# Down_Main_Board.net
KiCad netlist of a schematic drawn in EAGLE
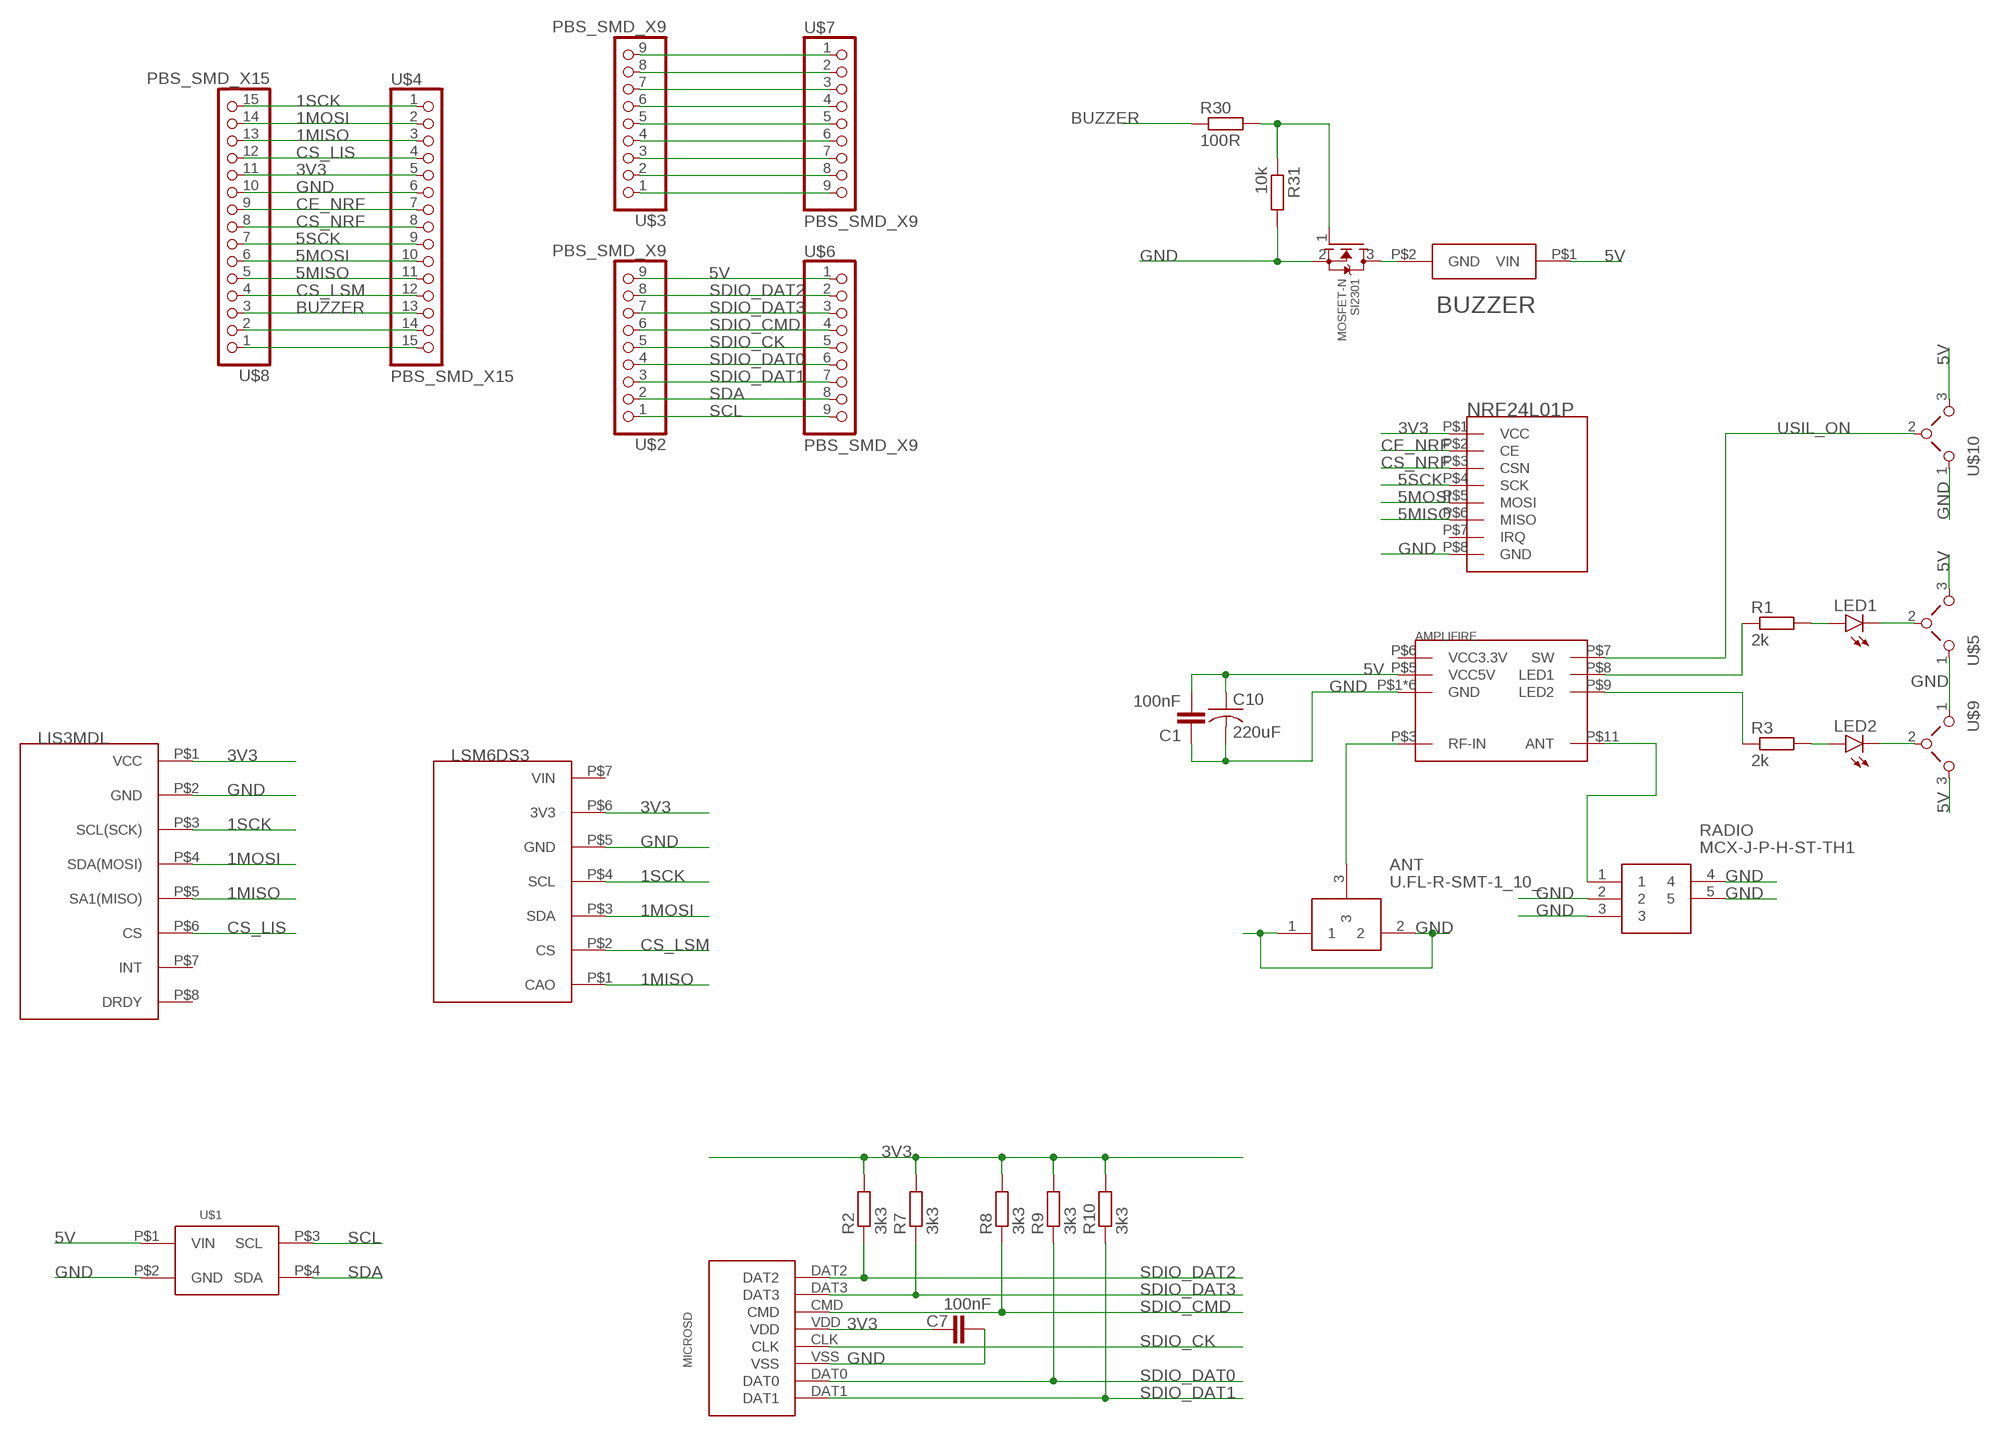
[diagram p0: schematic, sheet 1]

(export (version "E")
  (design (tool "Eeschema 10.0.6"))
  (components
    (comp (ref "AMPLIFIRE")
      (value "XQ-02A")
      (footprint "eagle-import:XQ-02A")
      (libsource (lib "eagle-import") (part "XQ-02A"))
    )
    (comp (ref "ANT")
      (value "U.FL-R-SMT-1_10_")
      (footprint "eagle-import:U.FL-R-SMT-1(10)")
      (fields
        (field (name "ARROW_PART_NUMBER") "U.FL-R-SMT-1(10)")
        (field (name "MOUSER_PART_NUMBER") "798-U.FL-R-SMT-110")
      )
      (libsource (lib "eagle-import") (part "U.FL-R-SMT-1_10_"))
    )
    (comp (ref "BUZZER")
      (value "BUZZERS8R6")
      (footprint "eagle-import:BUZZER-S8R12")
      (libsource (lib "eagle-import") (part "BUZZERS8R6"))
    )
    (comp (ref "C1")
      (value "100nF")
      (footprint "eagle-import:C0603")
      (libsource (lib "eagle-import") (part "C-EUC0603"))
    )
    (comp (ref "C7")
      (value "100nF")
      (footprint "eagle-import:C0603")
      (libsource (lib "eagle-import") (part "C-EUC0603"))
    )
    (comp (ref "C10")
      (value "220uF")
      (footprint "eagle-import:ECAP220-CMD")
      (libsource (lib "eagle-import") (part "ECAPECAP220"))
    )
    (comp (ref "LED1")
      (value "LEDCHIPLED_0603")
      (footprint "eagle-import:CHIPLED_0603")
      (libsource (lib "eagle-import") (part "LEDCHIPLED_0603"))
    )
    (comp (ref "LED2")
      (value "LEDCHIPLED_0603")
      (footprint "eagle-import:CHIPLED_0603")
      (libsource (lib "eagle-import") (part "LEDCHIPLED_0603"))
    )
    (comp (ref "LIS3MDL")
      (value "LIS3MDL-CJMCUбез_отв.")
      (footprint "eagle-import:LIS3MDL-CGMSU-NB2023-1")
      (libsource (lib "eagle-import") (part "LIS3MDL-CJMCUбез_отв."))
    )
    (comp (ref "LSM6DS3")
      (value "LSM6DS3-GY-NB2023")
      (footprint "eagle-import:LSM6DS3-GY-NB2023")
      (libsource (lib "eagle-import") (part "LSM6DS3-GY-NB2023"))
    )
    (comp (ref "MICROSD")
      (value "SD")
      (footprint "eagle-import:SD")
      (libsource (lib "eagle-import") (part "SD"))
    )
    (comp (ref "NRF24L01P")
      (value "NRF24L01_ML01SP4")
      (footprint "eagle-import:NRF24L01_ML01SP4")
      (libsource (lib "eagle-import") (part "NRF24L01_ML01SP4"))
    )
    (comp (ref "R1")
      (value "2k")
      (footprint "eagle-import:R0603")
      (libsource (lib "eagle-import") (part "R-EU_R0603"))
    )
    (comp (ref "R2")
      (value "3k3")
      (footprint "eagle-import:R0603")
      (libsource (lib "eagle-import") (part "R-EU_R0603"))
    )
    (comp (ref "R3")
      (value "2k")
      (footprint "eagle-import:R0603")
      (libsource (lib "eagle-import") (part "R-EU_R0603"))
    )
    (comp (ref "R7")
      (value "3k3")
      (footprint "eagle-import:R0603")
      (libsource (lib "eagle-import") (part "R-EU_R0603"))
    )
    (comp (ref "R8")
      (value "3k3")
      (footprint "eagle-import:R0603")
      (libsource (lib "eagle-import") (part "R-EU_R0603"))
    )
    (comp (ref "R9")
      (value "3k3")
      (footprint "eagle-import:R0603")
      (libsource (lib "eagle-import") (part "R-EU_R0603"))
    )
    (comp (ref "R10")
      (value "3k3")
      (footprint "eagle-import:R0603")
      (libsource (lib "eagle-import") (part "R-EU_R0603"))
    )
    (comp (ref "R30")
      (value "100R")
      (footprint "eagle-import:R0603")
      (libsource (lib "eagle-import") (part "R-EU_R0603"))
    )
    (comp (ref "R31")
      (value "10k")
      (footprint "eagle-import:R0603")
      (libsource (lib "eagle-import") (part "R-EU_R0603"))
    )
    (comp (ref "RADIO")
      (value "MCX-J-P-H-ST-TH1")
      (footprint "eagle-import:MCXJPHSTTH1")
      (fields (field (name "MOUSER_PART_NUMBER") "200-MCXJPHSTTH1"))
      (libsource (lib "eagle-import") (part "MCX-J-P-H-ST-TH1"))
    )
    (comp (ref "SI2301")
      (value "MOSFET-N")
      (footprint "eagle-import:SOT23-3")
      (libsource (lib "eagle-import") (part "MOSFET-N"))
    )
    (comp (ref "U$1")
      (value "BME280BME280-PINS-ONLY")
      (footprint "eagle-import:BME280-PINS-ONLY")
      (libsource (lib "eagle-import") (part "BME280BME280-PINS-ONLY"))
    )
    (comp (ref "U$2")
      (value "PBS_SMD_X9")
      (footprint "eagle-import:PBS_SMD_X9")
      (libsource (lib "eagle-import") (part "PBS_SMD_X9"))
    )
    (comp (ref "U$3")
      (value "PBS_SMD_X9")
      (footprint "eagle-import:PBS_SMD_X9")
      (libsource (lib "eagle-import") (part "PBS_SMD_X9"))
    )
    (comp (ref "U$4")
      (value "PBS_SMD_X15")
      (footprint "eagle-import:PBD_SMD_X15")
      (libsource (lib "eagle-import") (part "PBS_SMD_X15"))
    )
    (comp (ref "U$5")
      (value "VIAS-SELECT")
      (footprint "eagle-import:VIAS-SELECT")
      (libsource (lib "eagle-import") (part "VIAS-SELECT"))
    )
    (comp (ref "U$6")
      (value "PBS_SMD_X9")
      (footprint "eagle-import:PBS_SMD_X9")
      (libsource (lib "eagle-import") (part "PBS_SMD_X9"))
    )
    (comp (ref "U$7")
      (value "PBS_SMD_X9")
      (footprint "eagle-import:PBS_SMD_X9")
      (libsource (lib "eagle-import") (part "PBS_SMD_X9"))
    )
    (comp (ref "U$8")
      (value "PBS_SMD_X15")
      (footprint "eagle-import:PBD_SMD_X15")
      (libsource (lib "eagle-import") (part "PBS_SMD_X15"))
    )
    (comp (ref "U$9")
      (value "VIAS-SELECT")
      (footprint "eagle-import:VIAS-SELECT")
      (libsource (lib "eagle-import") (part "VIAS-SELECT"))
    )
    (comp (ref "U$10")
      (value "VIAS-SELECT")
      (footprint "eagle-import:VIAS-SELECT")
      (libsource (lib "eagle-import") (part "VIAS-SELECT"))
    )
  )
  (nets
    (net (code "1") (name "/1MISO") (class "Default")
      (node (ref "LIS3MDL") (pin "P$5") (pinfunction "SA1(MISO)_P$5") (pintype "bidirectional"))
      (node (ref "LSM6DS3") (pin "P$1") (pinfunction "CAO_P$1") (pintype "bidirectional"))
      (node (ref "U$4") (pin "3") (pinfunction "3_3") (pintype "passive"))
      (node (ref "U$8") (pin "13") (pinfunction "13_13") (pintype "passive"))
    )
    (net (code "2") (name "/1MOSI") (class "Default")
      (node (ref "LIS3MDL") (pin "P$4") (pinfunction "SDA(MOSI)_P$4") (pintype "bidirectional"))
      (node (ref "LSM6DS3") (pin "P$3") (pinfunction "SDA_P$3") (pintype "bidirectional"))
      (node (ref "U$4") (pin "2") (pinfunction "2_2") (pintype "passive"))
      (node (ref "U$8") (pin "14") (pinfunction "14_14") (pintype "passive"))
    )
    (net (code "3") (name "/1SCK") (class "Default")
      (node (ref "LIS3MDL") (pin "P$3") (pinfunction "SCL(SCK)_P$3") (pintype "bidirectional"))
      (node (ref "LSM6DS3") (pin "P$4") (pinfunction "SCL_P$4") (pintype "bidirectional"))
      (node (ref "U$4") (pin "1") (pinfunction "1_1") (pintype "passive"))
      (node (ref "U$8") (pin "15") (pinfunction "15_15") (pintype "passive"))
    )
    (net (code "4") (name "/3V3") (class "Default")
      (node (ref "C7") (pin "2") (pinfunction "2_2") (pintype "passive"))
      (node (ref "LIS3MDL") (pin "P$1") (pinfunction "VCC_P$1") (pintype "bidirectional"))
      (node (ref "LSM6DS3") (pin "P$6") (pinfunction "3V3_P$6") (pintype "bidirectional"))
      (node (ref "MICROSD") (pin "VDD") (pinfunction "VDD_VDD") (pintype "bidirectional"))
      (node (ref "NRF24L01P") (pin "P$1") (pinfunction "VCC_P$1") (pintype "bidirectional"))
      (node (ref "R10") (pin "2") (pinfunction "2_2") (pintype "passive"))
      (node (ref "R2") (pin "2") (pinfunction "2_2") (pintype "passive"))
      (node (ref "R7") (pin "2") (pinfunction "2_2") (pintype "passive"))
      (node (ref "R8") (pin "2") (pinfunction "2_2") (pintype "passive"))
      (node (ref "R9") (pin "2") (pinfunction "2_2") (pintype "passive"))
      (node (ref "U$4") (pin "5") (pinfunction "5_5") (pintype "passive"))
      (node (ref "U$8") (pin "11") (pinfunction "11_11") (pintype "passive"))
    )
    (net (code "5") (name "/5MISO") (class "Default")
      (node (ref "NRF24L01P") (pin "P$6") (pinfunction "MISO_P$6") (pintype "bidirectional"))
      (node (ref "U$4") (pin "11") (pinfunction "11_11") (pintype "passive"))
      (node (ref "U$8") (pin "5") (pinfunction "5_5") (pintype "passive"))
    )
    (net (code "6") (name "/5MOSI") (class "Default")
      (node (ref "NRF24L01P") (pin "P$5") (pinfunction "MOSI_P$5") (pintype "bidirectional"))
      (node (ref "U$4") (pin "10") (pinfunction "10_10") (pintype "passive"))
      (node (ref "U$8") (pin "6") (pinfunction "6_6") (pintype "passive"))
    )
    (net (code "7") (name "/5SCK") (class "Default")
      (node (ref "NRF24L01P") (pin "P$4") (pinfunction "SCK_P$4") (pintype "bidirectional"))
      (node (ref "U$4") (pin "9") (pinfunction "9_9") (pintype "passive"))
      (node (ref "U$8") (pin "7") (pinfunction "7_7") (pintype "passive"))
    )
    (net (code "8") (name "/5V") (class "Default")
      (node (ref "AMPLIFIRE") (pin "P$5") (pinfunction "VCC5V_P$5") (pintype "bidirectional"))
      (node (ref "BUZZER") (pin "P$1") (pinfunction "VIN_P$1") (pintype "bidirectional"))
      (node (ref "C1") (pin "2") (pinfunction "2_2") (pintype "passive"))
      (node (ref "C10") (pin "P$1") (pinfunction "1_P$1") (pintype "passive"))
      (node (ref "U$1") (pin "P$1") (pinfunction "VIN_P$1") (pintype "bidirectional"))
      (node (ref "U$10") (pin "3") (pinfunction "RIGHT_3") (pintype "passive"))
      (node (ref "U$2") (pin "9") (pinfunction "9_9") (pintype "passive"))
      (node (ref "U$5") (pin "3") (pinfunction "RIGHT_3") (pintype "passive"))
      (node (ref "U$6") (pin "1") (pinfunction "1_1") (pintype "passive"))
      (node (ref "U$9") (pin "3") (pinfunction "RIGHT_3") (pintype "passive"))
    )
    (net (code "9") (name "/BUZZER") (class "Default")
      (node (ref "R30") (pin "1") (pinfunction "1_1") (pintype "passive"))
      (node (ref "U$4") (pin "13") (pinfunction "13_13") (pintype "passive"))
      (node (ref "U$8") (pin "3") (pinfunction "3_3") (pintype "passive"))
    )
    (net (code "10") (name "/CE_NRF") (class "Default")
      (node (ref "NRF24L01P") (pin "P$2") (pinfunction "CE_P$2") (pintype "bidirectional"))
      (node (ref "U$4") (pin "7") (pinfunction "7_7") (pintype "passive"))
      (node (ref "U$8") (pin "9") (pinfunction "9_9") (pintype "passive"))
    )
    (net (code "11") (name "/CS_LIS") (class "Default")
      (node (ref "LIS3MDL") (pin "P$6") (pinfunction "CS_P$6") (pintype "bidirectional"))
      (node (ref "U$4") (pin "4") (pinfunction "4_4") (pintype "passive"))
      (node (ref "U$8") (pin "12") (pinfunction "12_12") (pintype "passive"))
    )
    (net (code "12") (name "/CS_LSM") (class "Default")
      (node (ref "LSM6DS3") (pin "P$2") (pinfunction "CS_P$2") (pintype "bidirectional"))
      (node (ref "U$4") (pin "12") (pinfunction "12_12") (pintype "passive"))
      (node (ref "U$8") (pin "4") (pinfunction "4_4") (pintype "passive"))
    )
    (net (code "13") (name "/CS_NRF") (class "Default")
      (node (ref "NRF24L01P") (pin "P$3") (pinfunction "CSN_P$3") (pintype "bidirectional"))
      (node (ref "U$4") (pin "8") (pinfunction "8_8") (pintype "passive"))
      (node (ref "U$8") (pin "8") (pinfunction "8_8") (pintype "passive"))
    )
    (net (code "14") (name "/GND") (class "Default")
      (node (ref "AMPLIFIRE") (pin "P$1") (pinfunction "GND_P$1") (pintype "bidirectional"))
      (node (ref "AMPLIFIRE") (pin "P$10") (pinfunction "GND_P$10") (pintype "bidirectional"))
      (node (ref "AMPLIFIRE") (pin "P$12") (pinfunction "GND_P$12") (pintype "bidirectional"))
      (node (ref "AMPLIFIRE") (pin "P$13") (pinfunction "GND_P$13") (pintype "bidirectional"))
      (node (ref "AMPLIFIRE") (pin "P$2") (pinfunction "GND_P$2") (pintype "bidirectional"))
      (node (ref "AMPLIFIRE") (pin "P$4") (pinfunction "GND_P$4") (pintype "bidirectional"))
      (node (ref "ANT") (pin "1") (pinfunction "1_1") (pintype "bidirectional"))
      (node (ref "ANT") (pin "2") (pinfunction "2_2") (pintype "bidirectional"))
      (node (ref "C1") (pin "1") (pinfunction "1_1") (pintype "passive"))
      (node (ref "C10") (pin "P$2") (pinfunction "2_P$2") (pintype "passive"))
      (node (ref "C7") (pin "1") (pinfunction "1_1") (pintype "passive"))
      (node (ref "LIS3MDL") (pin "P$2") (pinfunction "GND_P$2") (pintype "bidirectional"))
      (node (ref "LSM6DS3") (pin "P$5") (pinfunction "GND_P$5") (pintype "bidirectional"))
      (node (ref "MICROSD") (pin "VSS") (pinfunction "VSS_VSS") (pintype "bidirectional"))
      (node (ref "NRF24L01P") (pin "P$8") (pinfunction "GND_P$8") (pintype "bidirectional"))
      (node (ref "R31") (pin "2") (pinfunction "2_2") (pintype "passive"))
      (node (ref "RADIO") (pin "2") (pinfunction "2_2") (pintype "bidirectional"))
      (node (ref "RADIO") (pin "3") (pinfunction "3_3") (pintype "bidirectional"))
      (node (ref "RADIO") (pin "4") (pinfunction "4_4") (pintype "bidirectional"))
      (node (ref "RADIO") (pin "5") (pinfunction "5_5") (pintype "bidirectional"))
      (node (ref "SI2301") (pin "2") (pinfunction "S_2") (pintype "bidirectional"))
      (node (ref "U$1") (pin "P$2") (pinfunction "GND_P$2") (pintype "bidirectional"))
      (node (ref "U$10") (pin "1") (pinfunction "LEFT_1") (pintype "passive"))
      (node (ref "U$4") (pin "6") (pinfunction "6_6") (pintype "passive"))
      (node (ref "U$5") (pin "1") (pinfunction "LEFT_1") (pintype "passive"))
      (node (ref "U$8") (pin "10") (pinfunction "10_10") (pintype "passive"))
      (node (ref "U$9") (pin "1") (pinfunction "LEFT_1") (pintype "passive"))
    )
    (net (code "15") (name "/SCL") (class "Default")
      (node (ref "U$1") (pin "P$3") (pinfunction "SCL_P$3") (pintype "bidirectional"))
      (node (ref "U$2") (pin "1") (pinfunction "1_1") (pintype "passive"))
      (node (ref "U$6") (pin "9") (pinfunction "9_9") (pintype "passive"))
    )
    (net (code "16") (name "/SDA") (class "Default")
      (node (ref "U$1") (pin "P$4") (pinfunction "SDA_P$4") (pintype "bidirectional"))
      (node (ref "U$2") (pin "2") (pinfunction "2_2") (pintype "passive"))
      (node (ref "U$6") (pin "8") (pinfunction "8_8") (pintype "passive"))
    )
    (net (code "17") (name "/SDIO_CK") (class "Default")
      (node (ref "MICROSD") (pin "CLK") (pinfunction "CLK_CLK") (pintype "bidirectional"))
      (node (ref "U$2") (pin "5") (pinfunction "5_5") (pintype "passive"))
      (node (ref "U$6") (pin "5") (pinfunction "5_5") (pintype "passive"))
    )
    (net (code "18") (name "/SDIO_CMD") (class "Default")
      (node (ref "MICROSD") (pin "CMD") (pinfunction "CMD_CMD") (pintype "bidirectional"))
      (node (ref "R8") (pin "1") (pinfunction "1_1") (pintype "passive"))
      (node (ref "U$2") (pin "6") (pinfunction "6_6") (pintype "passive"))
      (node (ref "U$6") (pin "4") (pinfunction "4_4") (pintype "passive"))
    )
    (net (code "19") (name "/SDIO_DAT0") (class "Default")
      (node (ref "MICROSD") (pin "DAT0") (pinfunction "DAT0_DAT0") (pintype "bidirectional"))
      (node (ref "R9") (pin "1") (pinfunction "1_1") (pintype "passive"))
      (node (ref "U$2") (pin "4") (pinfunction "4_4") (pintype "passive"))
      (node (ref "U$6") (pin "6") (pinfunction "6_6") (pintype "passive"))
    )
    (net (code "20") (name "/SDIO_DAT1") (class "Default")
      (node (ref "MICROSD") (pin "DAT1") (pinfunction "DAT1_DAT1") (pintype "bidirectional"))
      (node (ref "R10") (pin "1") (pinfunction "1_1") (pintype "passive"))
      (node (ref "U$2") (pin "3") (pinfunction "3_3") (pintype "passive"))
      (node (ref "U$6") (pin "7") (pinfunction "7_7") (pintype "passive"))
    )
    (net (code "21") (name "/SDIO_DAT2") (class "Default")
      (node (ref "MICROSD") (pin "DAT2") (pinfunction "DAT2_DAT2") (pintype "bidirectional"))
      (node (ref "R2") (pin "1") (pinfunction "1_1") (pintype "passive"))
      (node (ref "U$2") (pin "8") (pinfunction "8_8") (pintype "passive"))
      (node (ref "U$6") (pin "2") (pinfunction "2_2") (pintype "passive"))
    )
    (net (code "22") (name "/SDIO_DAT3") (class "Default")
      (node (ref "MICROSD") (pin "DAT3") (pinfunction "DAT3_DAT3") (pintype "bidirectional"))
      (node (ref "R7") (pin "1") (pinfunction "1_1") (pintype "passive"))
      (node (ref "U$2") (pin "7") (pinfunction "7_7") (pintype "passive"))
      (node (ref "U$6") (pin "3") (pinfunction "3_3") (pintype "passive"))
    )
    (net (code "23") (name "/USIL_ON") (class "Default")
      (node (ref "AMPLIFIRE") (pin "P$7") (pinfunction "SW_P$7") (pintype "bidirectional"))
      (node (ref "U$10") (pin "2") (pinfunction "TOP_2") (pintype "passive"))
    )
    (net (code "24") (name "Net-(AMPLIFIRE-ANT)") (class "Default")
      (node (ref "AMPLIFIRE") (pin "P$11") (pinfunction "ANT_P$11") (pintype "bidirectional"))
      (node (ref "RADIO") (pin "1") (pinfunction "1_1") (pintype "bidirectional"))
    )
    (net (code "25") (name "Net-(AMPLIFIRE-LED1)") (class "Default")
      (node (ref "AMPLIFIRE") (pin "P$8") (pinfunction "LED1_P$8") (pintype "bidirectional"))
      (node (ref "R1") (pin "1") (pinfunction "1_1") (pintype "passive"))
    )
    (net (code "26") (name "Net-(AMPLIFIRE-LED2)") (class "Default")
      (node (ref "AMPLIFIRE") (pin "P$9") (pinfunction "LED2_P$9") (pintype "bidirectional"))
      (node (ref "R3") (pin "1") (pinfunction "1_1") (pintype "passive"))
    )
    (net (code "27") (name "Net-(AMPLIFIRE-RF-IN)") (class "Default")
      (node (ref "AMPLIFIRE") (pin "P$3") (pinfunction "RF-IN_P$3") (pintype "bidirectional"))
      (node (ref "ANT") (pin "3") (pinfunction "3_3") (pintype "bidirectional"))
    )
    (net (code "28") (name "Net-(BUZZER-GND)") (class "Default")
      (node (ref "BUZZER") (pin "P$2") (pinfunction "GND_P$2") (pintype "bidirectional"))
      (node (ref "SI2301") (pin "3") (pinfunction "D_3") (pintype "bidirectional"))
    )
    (net (code "29") (name "Net-(LED1-PadA)") (class "Default")
      (node (ref "LED1") (pin "A") (pinfunction "A_A") (pintype "passive"))
      (node (ref "R1") (pin "2") (pinfunction "2_2") (pintype "passive"))
    )
    (net (code "30") (name "Net-(LED2-PadA)") (class "Default")
      (node (ref "LED2") (pin "A") (pinfunction "A_A") (pintype "passive"))
      (node (ref "R3") (pin "2") (pinfunction "2_2") (pintype "passive"))
    )
    (net (code "31") (name "Net-(SI2301-G)") (class "Default")
      (node (ref "R30") (pin "2") (pinfunction "2_2") (pintype "passive"))
      (node (ref "R31") (pin "1") (pinfunction "1_1") (pintype "passive"))
      (node (ref "SI2301") (pin "1") (pinfunction "G_1") (pintype "bidirectional"))
    )
    (net (code "32") (name "Net-(U$3-Pad1)") (class "Default")
      (node (ref "U$3") (pin "1") (pinfunction "1_1") (pintype "passive"))
      (node (ref "U$7") (pin "9") (pinfunction "9_9") (pintype "passive"))
    )
    (net (code "33") (name "Net-(U$3-Pad2)") (class "Default")
      (node (ref "U$3") (pin "2") (pinfunction "2_2") (pintype "passive"))
      (node (ref "U$7") (pin "8") (pinfunction "8_8") (pintype "passive"))
    )
    (net (code "34") (name "Net-(U$3-Pad3)") (class "Default")
      (node (ref "U$3") (pin "3") (pinfunction "3_3") (pintype "passive"))
      (node (ref "U$7") (pin "7") (pinfunction "7_7") (pintype "passive"))
    )
    (net (code "35") (name "Net-(U$3-Pad4)") (class "Default")
      (node (ref "U$3") (pin "4") (pinfunction "4_4") (pintype "passive"))
      (node (ref "U$7") (pin "6") (pinfunction "6_6") (pintype "passive"))
    )
    (net (code "36") (name "Net-(U$3-Pad5)") (class "Default")
      (node (ref "U$3") (pin "5") (pinfunction "5_5") (pintype "passive"))
      (node (ref "U$7") (pin "5") (pinfunction "5_5") (pintype "passive"))
    )
    (net (code "37") (name "Net-(U$3-Pad6)") (class "Default")
      (node (ref "U$3") (pin "6") (pinfunction "6_6") (pintype "passive"))
      (node (ref "U$7") (pin "4") (pinfunction "4_4") (pintype "passive"))
    )
    (net (code "38") (name "Net-(U$3-Pad7)") (class "Default")
      (node (ref "U$3") (pin "7") (pinfunction "7_7") (pintype "passive"))
      (node (ref "U$7") (pin "3") (pinfunction "3_3") (pintype "passive"))
    )
    (net (code "39") (name "Net-(U$3-Pad8)") (class "Default")
      (node (ref "U$3") (pin "8") (pinfunction "8_8") (pintype "passive"))
      (node (ref "U$7") (pin "2") (pinfunction "2_2") (pintype "passive"))
    )
    (net (code "40") (name "Net-(U$3-Pad9)") (class "Default")
      (node (ref "U$3") (pin "9") (pinfunction "9_9") (pintype "passive"))
      (node (ref "U$7") (pin "1") (pinfunction "1_1") (pintype "passive"))
    )
    (net (code "41") (name "Net-(U$4-Pad14)") (class "Default")
      (node (ref "U$4") (pin "14") (pinfunction "14_14") (pintype "passive"))
      (node (ref "U$8") (pin "2") (pinfunction "2_2") (pintype "passive"))
    )
    (net (code "42") (name "Net-(U$4-Pad15)") (class "Default")
      (node (ref "U$4") (pin "15") (pinfunction "15_15") (pintype "passive"))
      (node (ref "U$8") (pin "1") (pinfunction "1_1") (pintype "passive"))
    )
    (net (code "43") (name "Net-(U$5-TOP)") (class "Default")
      (node (ref "LED1") (pin "C") (pinfunction "C_C") (pintype "passive"))
      (node (ref "U$5") (pin "2") (pinfunction "TOP_2") (pintype "passive"))
    )
    (net (code "44") (name "Net-(U$9-TOP)") (class "Default")
      (node (ref "LED2") (pin "C") (pinfunction "C_C") (pintype "passive"))
      (node (ref "U$9") (pin "2") (pinfunction "TOP_2") (pintype "passive"))
    )
    (net (code "45") (name "unconnected-(AMPLIFIRE-VCC3.3V-PadP$6)") (class "Default")
      (node (ref "AMPLIFIRE") (pin "P$6") (pinfunction "VCC3.3V_P$6") (pintype "bidirectional"))
    )
    (net (code "46") (name "unconnected-(LIS3MDL-DRDY-PadP$8)") (class "Default")
      (node (ref "LIS3MDL") (pin "P$8") (pinfunction "DRDY_P$8") (pintype "bidirectional"))
    )
    (net (code "47") (name "unconnected-(LIS3MDL-INT-PadP$7)") (class "Default")
      (node (ref "LIS3MDL") (pin "P$7") (pinfunction "INT_P$7") (pintype "bidirectional"))
    )
    (net (code "48") (name "unconnected-(LSM6DS3-VIN-PadP$7)") (class "Default")
      (node (ref "LSM6DS3") (pin "P$7") (pinfunction "VIN_P$7") (pintype "bidirectional"))
    )
    (net (code "49") (name "unconnected-(NRF24L01P-IRQ-PadP$7)") (class "Default")
      (node (ref "NRF24L01P") (pin "P$7") (pinfunction "IRQ_P$7") (pintype "bidirectional"))
    )
  )
)
